# OV7725.net
KiCad netlist of a schematic drawn in EAGLE
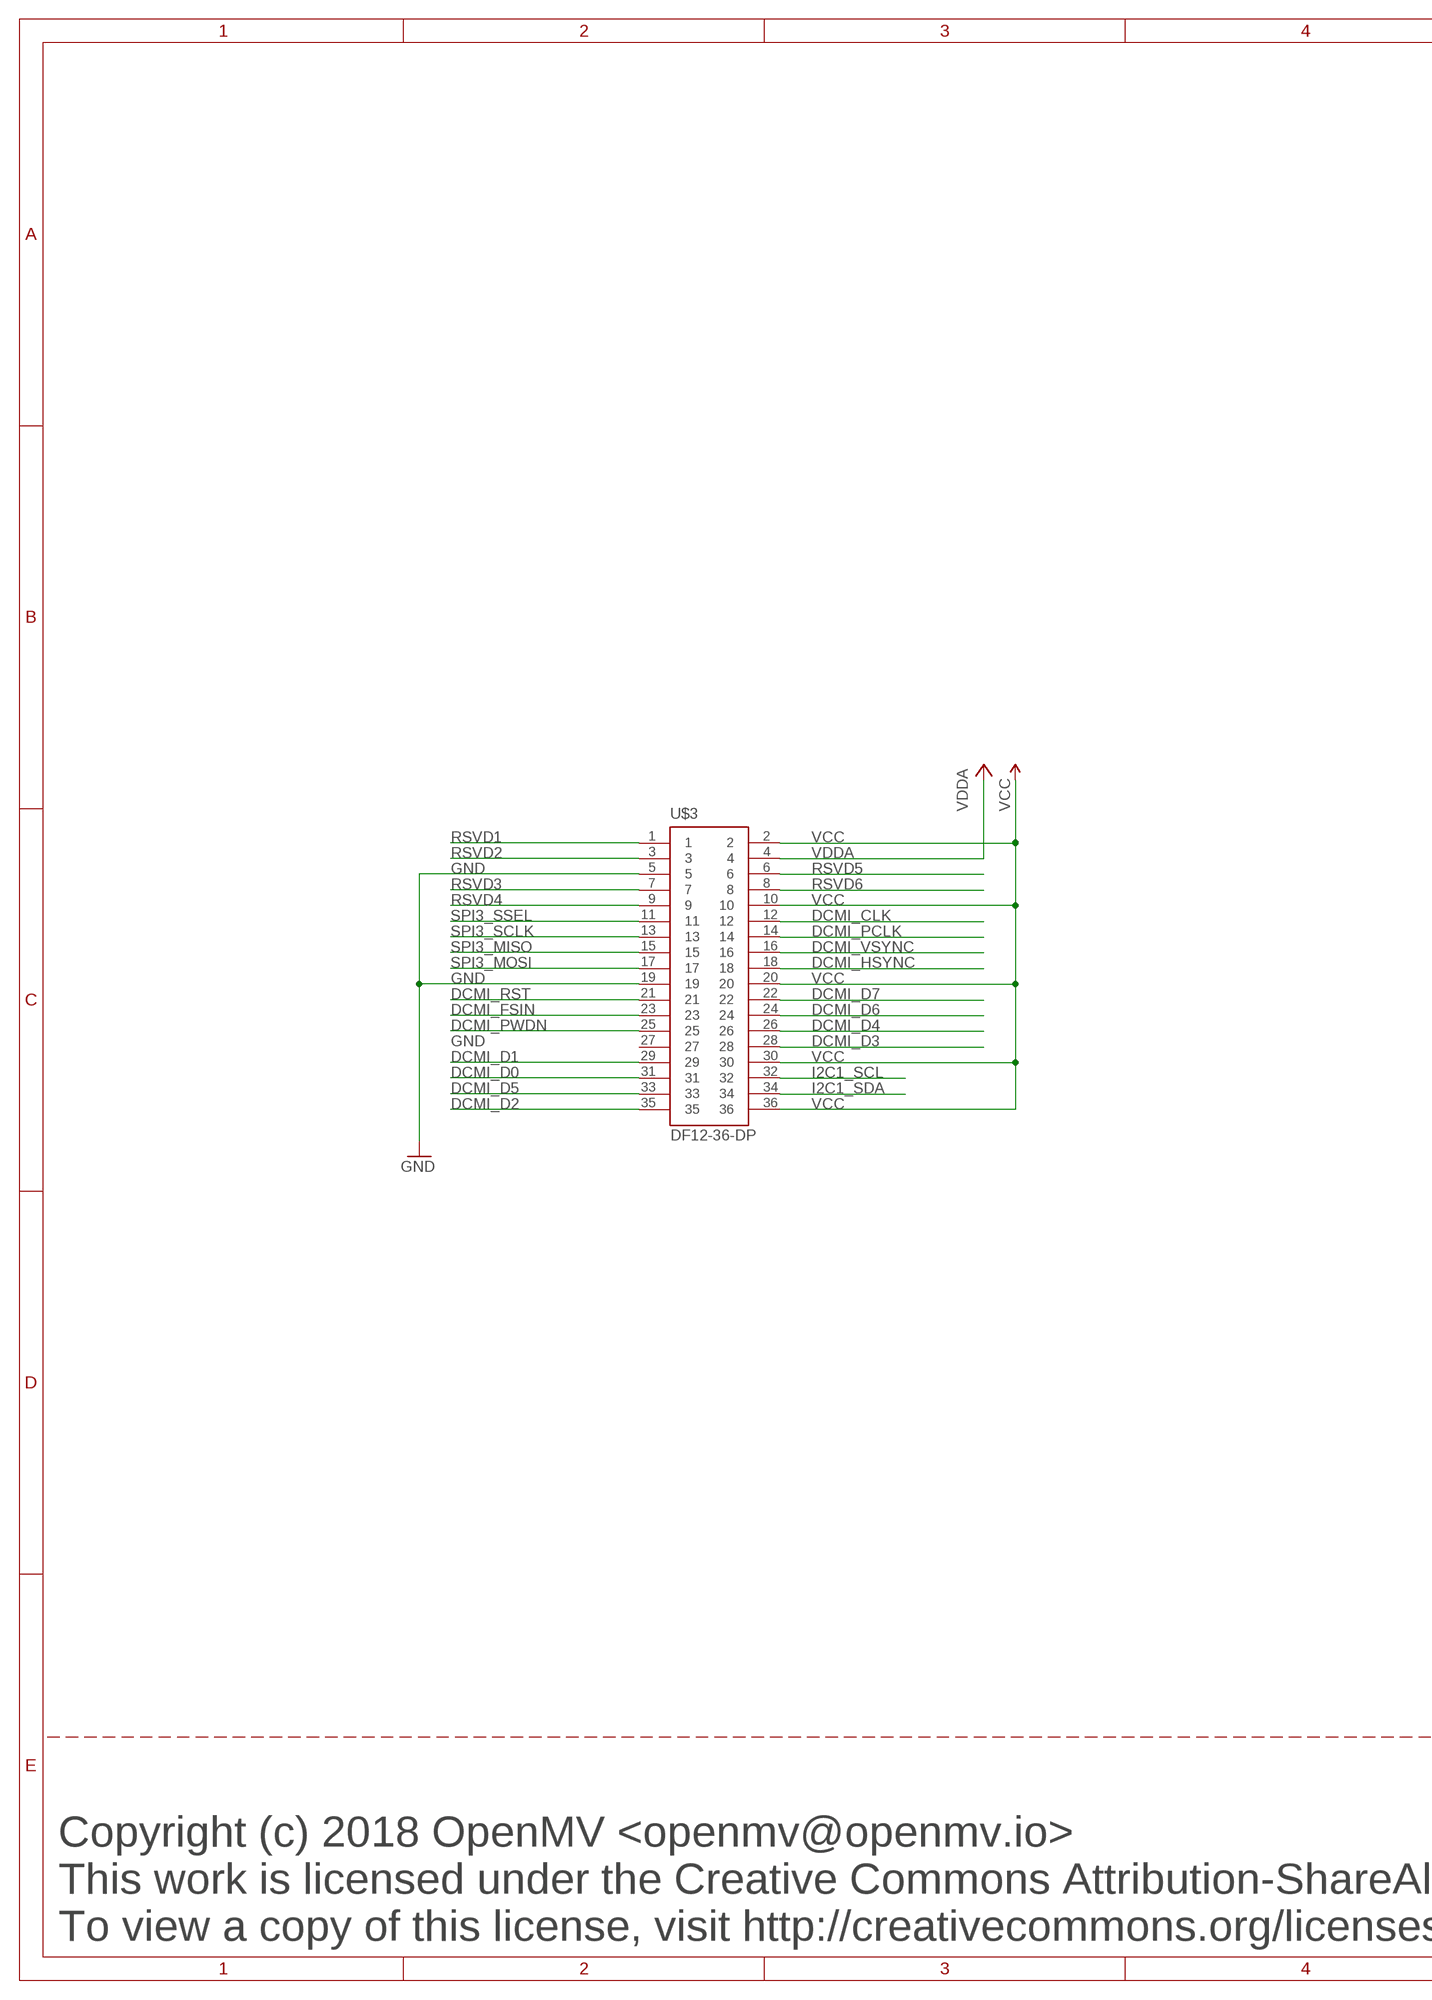
[diagram p0: schematic, sheet 1, part 1 of 2]
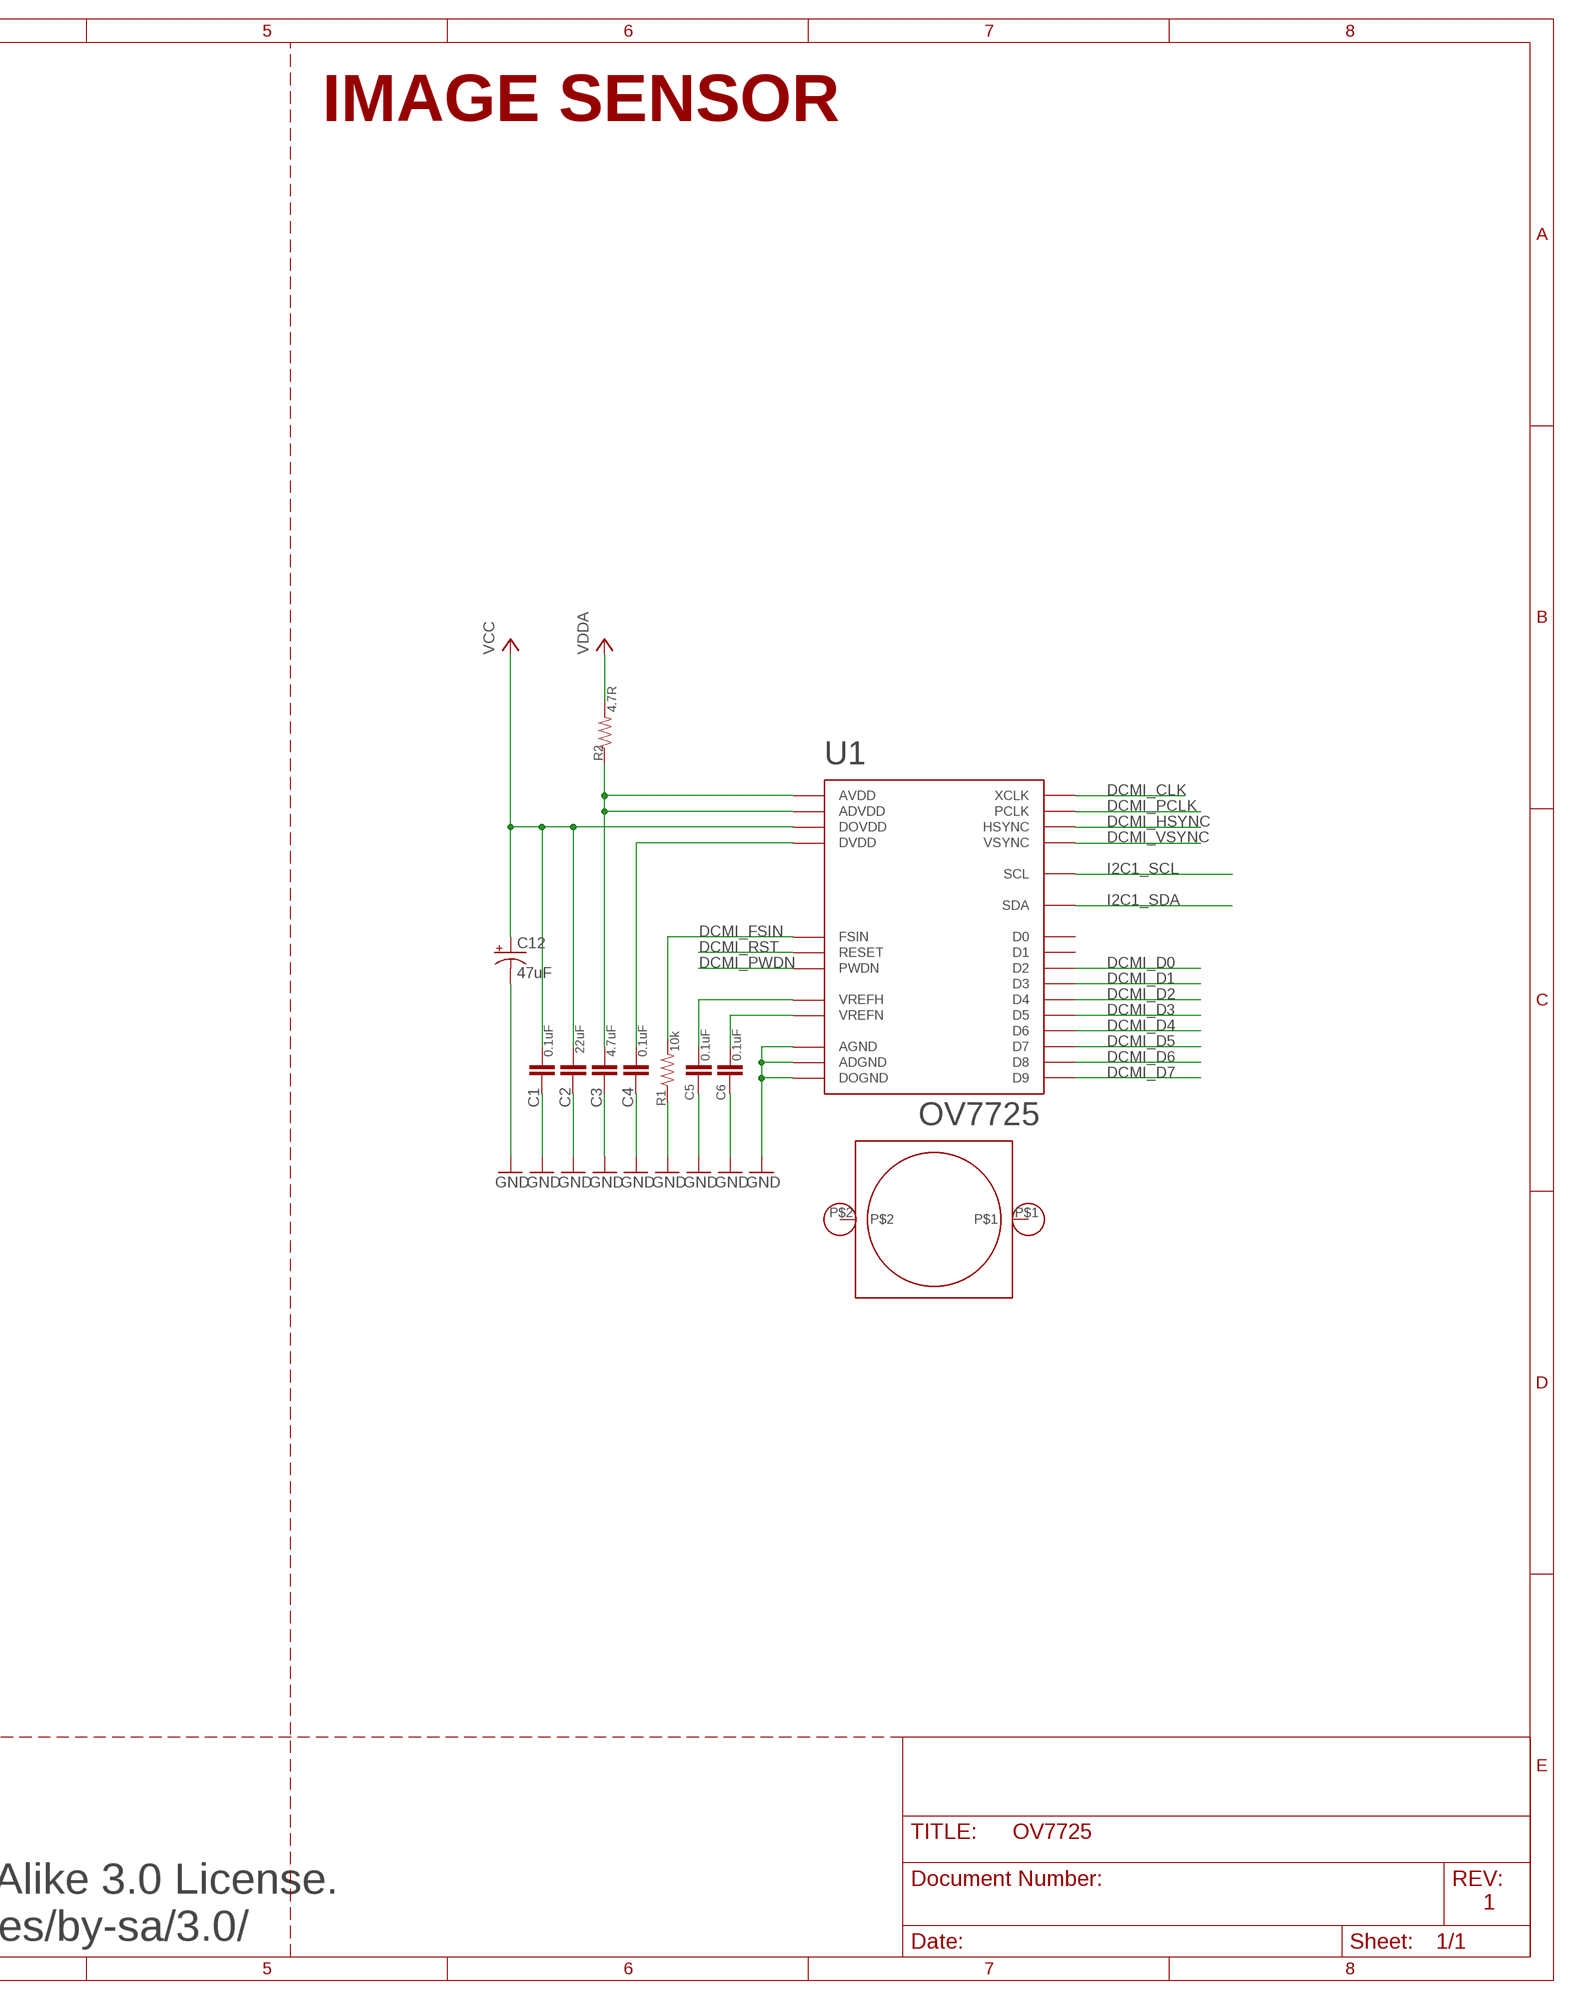
[diagram p1: schematic, sheet 1, part 2 of 2]

(export (version "E")
  (design (tool "Eeschema 10.0.6"))
  (components
    (comp (ref "C1")
      (value "0.1uF")
      (footprint "eagle-import:0603-CAP")
      (libsource (lib "eagle-import") (part "CAP0603-CAP"))
    )
    (comp (ref "C2")
      (value "22uF")
      (footprint "eagle-import:0805")
      (libsource (lib "eagle-import") (part "CAP0805"))
    )
    (comp (ref "C3")
      (value "4.7uF")
      (footprint "eagle-import:0603-CAP")
      (libsource (lib "eagle-import") (part "CAP0603-CAP"))
    )
    (comp (ref "C4")
      (value "0.1uF")
      (footprint "eagle-import:0603-CAP")
      (libsource (lib "eagle-import") (part "CAP0603-CAP"))
    )
    (comp (ref "C5")
      (value "0.1uF")
      (footprint "eagle-import:0603-CAP")
      (libsource (lib "eagle-import") (part "CAP0603-CAP"))
    )
    (comp (ref "C6")
      (value "0.1uF")
      (footprint "eagle-import:0603-CAP")
      (libsource (lib "eagle-import") (part "CAP0603-CAP"))
    )
    (comp (ref "C12")
      (value "47uF")
      (footprint "eagle-import:EIA3216")
      (libsource (lib "eagle-import") (part "CAP_POL1206"))
    )
    (comp (ref "LM1")
      (value "LENSMOUNT20MM")
      (footprint "eagle-import:LENSMOUNT-20MM")
      (libsource (lib "eagle-import") (part "LENSMOUNT20MM"))
    )
    (comp (ref "R1")
      (value "10k")
      (footprint "eagle-import:0603-RES")
      (libsource (lib "eagle-import") (part "RESISTOR0603-RES"))
    )
    (comp (ref "R2")
      (value "4.7R")
      (footprint "eagle-import:0603-RES")
      (libsource (lib "eagle-import") (part "RESISTOR0603-RES"))
    )
    (comp (ref "U$3")
      (value "DF12-36-DP")
      (footprint "eagle-import:DF12-36-DP")
      (libsource (lib "eagle-import") (part "DF12-36-DP"))
    )
    (comp (ref "U1")
      (value "OV7725")
      (footprint "eagle-import:CSP2-28")
      (libsource (lib "eagle-import") (part "OV7725"))
    )
  )
  (nets
    (net (code "1") (name "/DCMI_CLK") (class "Default")
      (node (ref "U$3") (pin "12") (pinfunction "12_12") (pintype "bidirectional"))
      (node (ref "U1") (pin "F3") (pinfunction "XCLK_F3") (pintype "bidirectional"))
    )
    (net (code "2") (name "/DCMI_D0") (class "Default")
      (node (ref "U$3") (pin "31") (pinfunction "31_31") (pintype "bidirectional"))
      (node (ref "U1") (pin "F5") (pinfunction "D2_F5") (pintype "bidirectional"))
    )
    (net (code "3") (name "/DCMI_D1") (class "Default")
      (node (ref "U$3") (pin "29") (pinfunction "29_29") (pintype "bidirectional"))
      (node (ref "U1") (pin "F2") (pinfunction "D3_F2") (pintype "bidirectional"))
    )
    (net (code "4") (name "/DCMI_D2") (class "Default")
      (node (ref "U$3") (pin "35") (pinfunction "35_35") (pintype "bidirectional"))
      (node (ref "U1") (pin "D6") (pinfunction "D4_D6") (pintype "bidirectional"))
    )
    (net (code "5") (name "/DCMI_D3") (class "Default")
      (node (ref "U$3") (pin "28") (pinfunction "28_28") (pintype "bidirectional"))
      (node (ref "U1") (pin "D1") (pinfunction "D5_D1") (pintype "bidirectional"))
    )
    (net (code "6") (name "/DCMI_D4") (class "Default")
      (node (ref "U$3") (pin "26") (pinfunction "26_26") (pintype "bidirectional"))
      (node (ref "U1") (pin "E6") (pinfunction "D6_E6") (pintype "bidirectional"))
    )
    (net (code "7") (name "/DCMI_D5") (class "Default")
      (node (ref "U$3") (pin "33") (pinfunction "33_33") (pintype "bidirectional"))
      (node (ref "U1") (pin "E1") (pinfunction "D7_E1") (pintype "bidirectional"))
    )
    (net (code "8") (name "/DCMI_D6") (class "Default")
      (node (ref "U$3") (pin "24") (pinfunction "24_24") (pintype "bidirectional"))
      (node (ref "U1") (pin "F6") (pinfunction "D8_F6") (pintype "bidirectional"))
    )
    (net (code "9") (name "/DCMI_D7") (class "Default")
      (node (ref "U$3") (pin "22") (pinfunction "22_22") (pintype "bidirectional"))
      (node (ref "U1") (pin "F1") (pinfunction "D9_F1") (pintype "bidirectional"))
    )
    (net (code "10") (name "/DCMI_FSIN") (class "Default")
      (node (ref "R1") (pin "2") (pinfunction "2_2") (pintype "passive"))
      (node (ref "U$3") (pin "23") (pinfunction "23_23") (pintype "bidirectional"))
      (node (ref "U1") (pin "A4") (pinfunction "FSIN_A4") (pintype "input"))
    )
    (net (code "11") (name "/DCMI_HSYNC") (class "Default")
      (node (ref "U$3") (pin "18") (pinfunction "18_18") (pintype "bidirectional"))
      (node (ref "U1") (pin "B6") (pinfunction "HSYNC_B6") (pintype "bidirectional"))
    )
    (net (code "12") (name "/DCMI_PCLK") (class "Default")
      (node (ref "U$3") (pin "14") (pinfunction "14_14") (pintype "bidirectional"))
      (node (ref "U1") (pin "E4") (pinfunction "PCLK_E4") (pintype "bidirectional"))
    )
    (net (code "13") (name "/DCMI_PWDN") (class "Default")
      (node (ref "U$3") (pin "25") (pinfunction "25_25") (pintype "bidirectional"))
      (node (ref "U1") (pin "C1") (pinfunction "PWDN_C1") (pintype "bidirectional"))
    )
    (net (code "14") (name "/DCMI_RST") (class "Default")
      (node (ref "U$3") (pin "21") (pinfunction "21_21") (pintype "bidirectional"))
      (node (ref "U1") (pin "A2") (pinfunction "RESET_A2") (pintype "bidirectional"))
    )
    (net (code "15") (name "/DCMI_VSYNC") (class "Default")
      (node (ref "U$3") (pin "16") (pinfunction "16_16") (pintype "bidirectional"))
      (node (ref "U1") (pin "C6") (pinfunction "VSYNC_C6") (pintype "bidirectional"))
    )
    (net (code "16") (name "/I2C1_SCL") (class "Default")
      (node (ref "U$3") (pin "32") (pinfunction "32_32") (pintype "bidirectional"))
      (node (ref "U1") (pin "A5") (pinfunction "SCL_A5") (pintype "bidirectional"))
    )
    (net (code "17") (name "/I2C1_SDA") (class "Default")
      (node (ref "U$3") (pin "34") (pinfunction "34_34") (pintype "bidirectional"))
      (node (ref "U1") (pin "B5") (pinfunction "SDA_B5") (pintype "bidirectional"))
    )
    (net (code "18") (name "/P$1") (class "Default")
      (node (ref "LM1") (pin "P$1") (pinfunction "P$1_P$1") (pintype "power_in"))
    )
    (net (code "19") (name "/P$2") (class "Default")
      (node (ref "LM1") (pin "P$2") (pinfunction "P$2_P$2") (pintype "power_in"))
    )
    (net (code "20") (name "/RSVD1") (class "Default")
      (node (ref "U$3") (pin "1") (pinfunction "1_1") (pintype "bidirectional"))
    )
    (net (code "21") (name "/RSVD2") (class "Default")
      (node (ref "U$3") (pin "3") (pinfunction "3_3") (pintype "bidirectional"))
    )
    (net (code "22") (name "/RSVD3") (class "Default")
      (node (ref "U$3") (pin "7") (pinfunction "7_7") (pintype "bidirectional"))
    )
    (net (code "23") (name "/RSVD4") (class "Default")
      (node (ref "U$3") (pin "9") (pinfunction "9_9") (pintype "bidirectional"))
    )
    (net (code "24") (name "/RSVD5") (class "Default")
      (node (ref "U$3") (pin "6") (pinfunction "6_6") (pintype "bidirectional"))
    )
    (net (code "25") (name "/RSVD6") (class "Default")
      (node (ref "U$3") (pin "8") (pinfunction "8_8") (pintype "bidirectional"))
    )
    (net (code "26") (name "/SPI3_MISO") (class "Default")
      (node (ref "U$3") (pin "15") (pinfunction "15_15") (pintype "bidirectional"))
    )
    (net (code "27") (name "/SPI3_MOSI") (class "Default")
      (node (ref "U$3") (pin "17") (pinfunction "17_17") (pintype "bidirectional"))
    )
    (net (code "28") (name "/SPI3_SCLK") (class "Default")
      (node (ref "U$3") (pin "13") (pinfunction "13_13") (pintype "bidirectional"))
    )
    (net (code "29") (name "/SPI3_SSEL") (class "Default")
      (node (ref "U$3") (pin "11") (pinfunction "11_11") (pintype "bidirectional"))
    )
    (net (code "30") (name "GND") (class "Default")
      (node (ref "C1") (pin "2") (pinfunction "2_2") (pintype "passive"))
      (node (ref "C12") (pin "C") (pinfunction "-_C") (pintype "passive"))
      (node (ref "C2") (pin "2") (pinfunction "2_2") (pintype "passive"))
      (node (ref "C3") (pin "2") (pinfunction "2_2") (pintype "passive"))
      (node (ref "C4") (pin "2") (pinfunction "2_2") (pintype "passive"))
      (node (ref "C5") (pin "2") (pinfunction "2_2") (pintype "passive"))
      (node (ref "C6") (pin "2") (pinfunction "2_2") (pintype "passive"))
      (node (ref "R1") (pin "1") (pinfunction "1_1") (pintype "passive"))
      (node (ref "U$3") (pin "19") (pinfunction "19_19") (pintype "bidirectional"))
      (node (ref "U$3") (pin "5") (pinfunction "5_5") (pintype "bidirectional"))
      (node (ref "U1") (pin "B1") (pinfunction "ADGND_B1") (pintype "power_in"))
      (node (ref "U1") (pin "B4") (pinfunction "AGND_B4") (pintype "power_in"))
      (node (ref "U1") (pin "F4") (pinfunction "DOGND_F4") (pintype "power_in"))
    )
    (net (code "31") (name "Net-(U1-ADVDD)") (class "Default")
      (node (ref "C3") (pin "1") (pinfunction "1_1") (pintype "passive"))
      (node (ref "R2") (pin "1") (pinfunction "1_1") (pintype "passive"))
      (node (ref "U1") (pin "A1") (pinfunction "ADVDD_A1") (pintype "power_in"))
      (node (ref "U1") (pin "B3") (pinfunction "AVDD_B3") (pintype "power_in"))
    )
    (net (code "32") (name "Net-(U1-DVDD)") (class "Default")
      (node (ref "C4") (pin "1") (pinfunction "1_1") (pintype "passive"))
      (node (ref "U1") (pin "E3") (pinfunction "DVDD_E3") (pintype "power_in"))
    )
    (net (code "33") (name "Net-(U1-VREFH)") (class "Default")
      (node (ref "C5") (pin "1") (pinfunction "1_1") (pintype "passive"))
      (node (ref "U1") (pin "A3") (pinfunction "VREFH_A3") (pintype "power_in"))
    )
    (net (code "34") (name "Net-(U1-VREFN)") (class "Default")
      (node (ref "C6") (pin "1") (pinfunction "1_1") (pintype "passive"))
      (node (ref "U1") (pin "B2") (pinfunction "VREFN_B2") (pintype "power_in"))
    )
    (net (code "35") (name "VCC") (class "Default")
      (node (ref "C1") (pin "1") (pinfunction "1_1") (pintype "passive"))
      (node (ref "C12") (pin "A") (pinfunction "+_A") (pintype "passive"))
      (node (ref "C2") (pin "1") (pinfunction "1_1") (pintype "passive"))
      (node (ref "U$3") (pin "10") (pinfunction "10_10") (pintype "bidirectional"))
      (node (ref "U$3") (pin "2") (pinfunction "2_2") (pintype "bidirectional"))
      (node (ref "U$3") (pin "20") (pinfunction "20_20") (pintype "bidirectional"))
      (node (ref "U$3") (pin "30") (pinfunction "30_30") (pintype "bidirectional"))
      (node (ref "U$3") (pin "36") (pinfunction "36_36") (pintype "bidirectional"))
      (node (ref "U1") (pin "E5") (pinfunction "DOVDD_E5") (pintype "power_in"))
    )
    (net (code "36") (name "VDDA") (class "Default")
      (node (ref "R2") (pin "2") (pinfunction "2_2") (pintype "passive"))
      (node (ref "U$3") (pin "4") (pinfunction "4_4") (pintype "bidirectional"))
    )
    (net (code "37") (name "unconnected-(U$3-Pad27)") (class "Default")
      (node (ref "U$3") (pin "27") (pinfunction "27_27") (pintype "bidirectional"))
    )
    (net (code "38") (name "unconnected-(U1-D0-PadA6)") (class "Default")
      (node (ref "U1") (pin "A6") (pinfunction "D0_A6") (pintype "bidirectional"))
    )
    (net (code "39") (name "unconnected-(U1-D1-PadE2)") (class "Default")
      (node (ref "U1") (pin "E2") (pinfunction "D1_E2") (pintype "bidirectional"))
    )
  )
)
